# ESC.net
KiCad netlist of a schematic drawn in Altium Designer
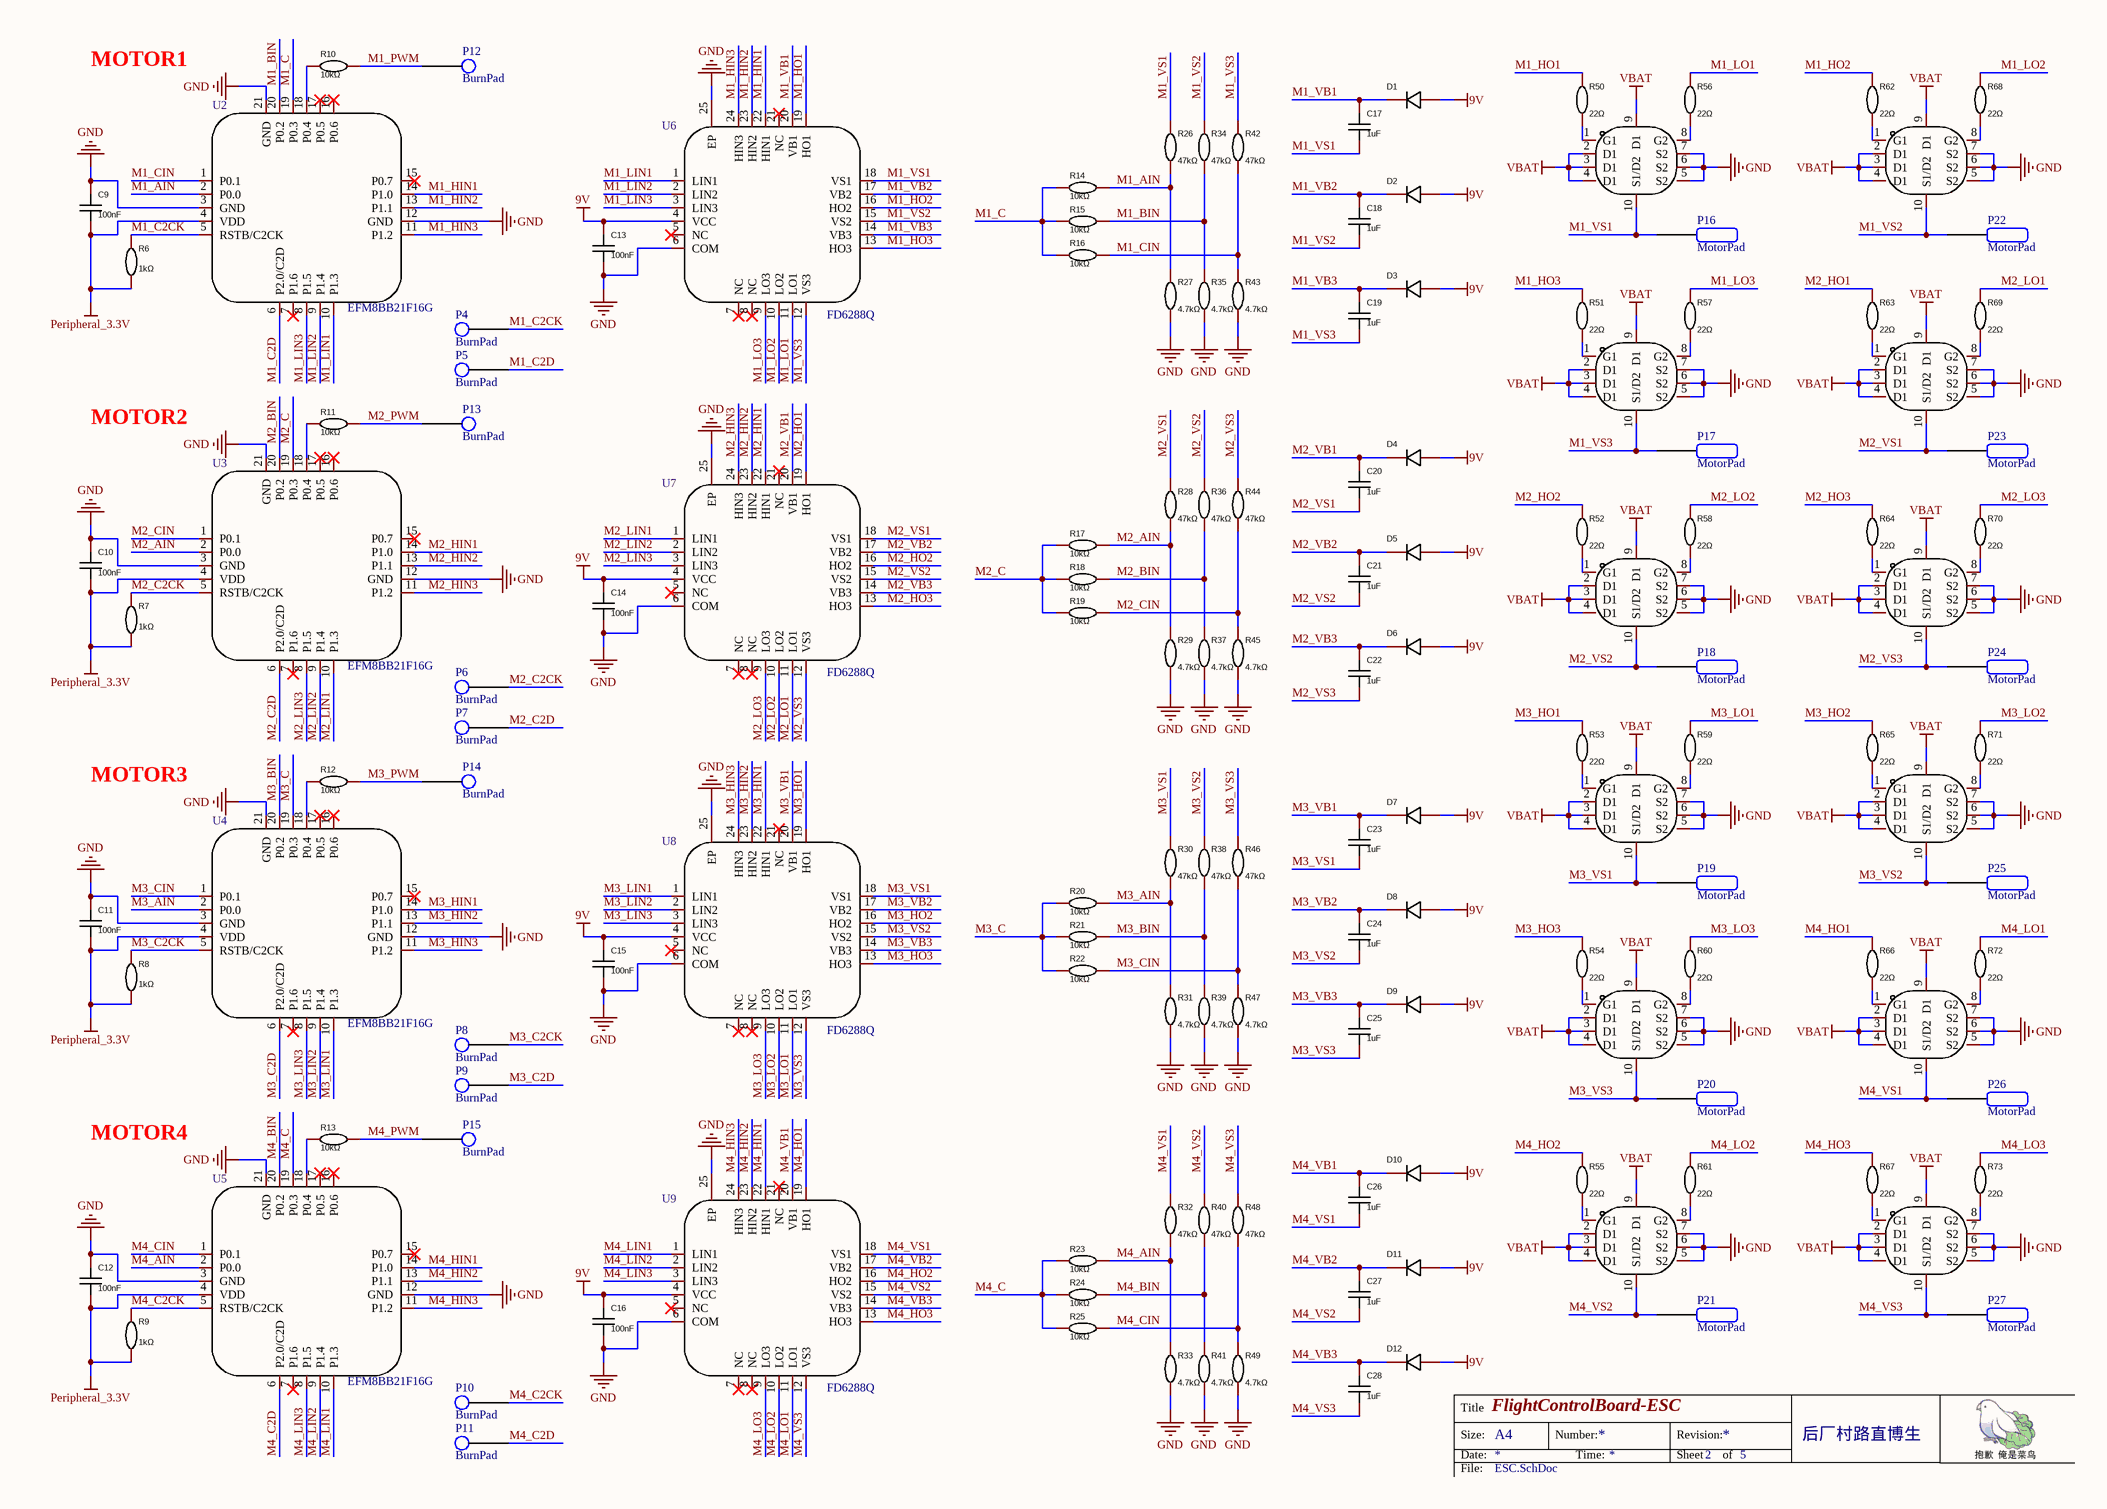
[diagram p0: ESC.SchDoc]

(export (version "E")
  (design (tool "Eeschema 10.0.6"))
  (components
    (comp (ref "C9")
      (value "100nF")
      (footprint "C0201")
      (libsource (lib "Capacitor") (part "CC0603KRX7R9BB104"))
    )
    (comp (ref "C10")
      (value "100nF")
      (footprint "C0201")
      (libsource (lib "Capacitor") (part "CC0603KRX7R9BB104"))
    )
    (comp (ref "C11")
      (value "100nF")
      (footprint "C0201")
      (libsource (lib "Capacitor") (part "CC0603KRX7R9BB104"))
    )
    (comp (ref "C12")
      (value "100nF")
      (footprint "C0201")
      (libsource (lib "Capacitor") (part "CC0603KRX7R9BB104"))
    )
    (comp (ref "C13")
      (value "100nF")
      (footprint "C0201")
      (libsource (lib "Capacitor") (part "CC0603KRX7R9BB104"))
    )
    (comp (ref "C14")
      (value "100nF")
      (footprint "C0201")
      (libsource (lib "Capacitor") (part "CC0603KRX7R9BB104"))
    )
    (comp (ref "C15")
      (value "100nF")
      (footprint "C0201")
      (libsource (lib "Capacitor") (part "CC0603KRX7R9BB104"))
    )
    (comp (ref "C16")
      (value "100nF")
      (footprint "C0201")
      (libsource (lib "Capacitor") (part "CC0603KRX7R9BB104"))
    )
    (comp (ref "C17")
      (value "1uF")
      (footprint "C0402")
      (libsource (lib "Capacitor") (part "CC0603KRX7R9BB104"))
    )
    (comp (ref "C18")
      (value "1uF")
      (footprint "C0402")
      (libsource (lib "Capacitor") (part "CC0603KRX7R9BB104"))
    )
    (comp (ref "C19")
      (value "1uF")
      (footprint "C0402")
      (libsource (lib "Capacitor") (part "CC0603KRX7R9BB104"))
    )
    (comp (ref "C20")
      (value "1uF")
      (footprint "C0402")
      (libsource (lib "Capacitor") (part "CC0603KRX7R9BB104"))
    )
    (comp (ref "C21")
      (value "1uF")
      (footprint "C0402")
      (libsource (lib "Capacitor") (part "CC0603KRX7R9BB104"))
    )
    (comp (ref "C22")
      (value "1uF")
      (footprint "C0402")
      (libsource (lib "Capacitor") (part "CC0603KRX7R9BB104"))
    )
    (comp (ref "C23")
      (value "1uF")
      (footprint "C0402")
      (libsource (lib "Capacitor") (part "CC0603KRX7R9BB104"))
    )
    (comp (ref "C24")
      (value "1uF")
      (footprint "C0402")
      (libsource (lib "Capacitor") (part "CC0603KRX7R9BB104"))
    )
    (comp (ref "C25")
      (value "1uF")
      (footprint "C0402")
      (libsource (lib "Capacitor") (part "CC0603KRX7R9BB104"))
    )
    (comp (ref "C26")
      (value "1uF")
      (footprint "C0402")
      (libsource (lib "Capacitor") (part "CC0603KRX7R9BB104"))
    )
    (comp (ref "C27")
      (value "1uF")
      (footprint "C0402")
      (libsource (lib "Capacitor") (part "CC0603KRX7R9BB104"))
    )
    (comp (ref "C28")
      (value "1uF")
      (footprint "C0402")
      (libsource (lib "Capacitor") (part "CC0603KRX7R9BB104"))
    )
    (comp (ref "D1")
      (value "1N4148WT T4")
      (footprint "SOD-523")
      (fields (field (name "MANUFACTURER") "CJ(江苏长电/长晶)"))
      (libsource (lib "Diode") (part "1N4148WT T4"))
    )
    (comp (ref "D2")
      (value "1N4148WT T4")
      (footprint "SOD-523")
      (fields (field (name "MANUFACTURER") "CJ(江苏长电/长晶)"))
      (libsource (lib "Diode") (part "1N4148WT T4"))
    )
    (comp (ref "D3")
      (value "1N4148WT T4")
      (footprint "SOD-523")
      (fields (field (name "MANUFACTURER") "CJ(江苏长电/长晶)"))
      (libsource (lib "Diode") (part "1N4148WT T4"))
    )
    (comp (ref "D4")
      (value "1N4148WT T4")
      (footprint "SOD-523")
      (fields (field (name "MANUFACTURER") "CJ(江苏长电/长晶)"))
      (libsource (lib "Diode") (part "1N4148WT T4"))
    )
    (comp (ref "D5")
      (value "1N4148WT T4")
      (footprint "SOD-523")
      (fields (field (name "MANUFACTURER") "CJ(江苏长电/长晶)"))
      (libsource (lib "Diode") (part "1N4148WT T4"))
    )
    (comp (ref "D6")
      (value "1N4148WT T4")
      (footprint "SOD-523")
      (fields (field (name "MANUFACTURER") "CJ(江苏长电/长晶)"))
      (libsource (lib "Diode") (part "1N4148WT T4"))
    )
    (comp (ref "D7")
      (value "1N4148WT T4")
      (footprint "SOD-523")
      (fields (field (name "MANUFACTURER") "CJ(江苏长电/长晶)"))
      (libsource (lib "Diode") (part "1N4148WT T4"))
    )
    (comp (ref "D8")
      (value "1N4148WT T4")
      (footprint "SOD-523")
      (fields (field (name "MANUFACTURER") "CJ(江苏长电/长晶)"))
      (libsource (lib "Diode") (part "1N4148WT T4"))
    )
    (comp (ref "D9")
      (value "1N4148WT T4")
      (footprint "SOD-523")
      (fields (field (name "MANUFACTURER") "CJ(江苏长电/长晶)"))
      (libsource (lib "Diode") (part "1N4148WT T4"))
    )
    (comp (ref "D10")
      (value "1N4148WT T4")
      (footprint "SOD-523")
      (fields (field (name "MANUFACTURER") "CJ(江苏长电/长晶)"))
      (libsource (lib "Diode") (part "1N4148WT T4"))
    )
    (comp (ref "D11")
      (value "1N4148WT T4")
      (footprint "SOD-523")
      (fields (field (name "MANUFACTURER") "CJ(江苏长电/长晶)"))
      (libsource (lib "Diode") (part "1N4148WT T4"))
    )
    (comp (ref "D12")
      (value "1N4148WT T4")
      (footprint "SOD-523")
      (fields (field (name "MANUFACTURER") "CJ(江苏长电/长晶)"))
      (libsource (lib "Diode") (part "1N4148WT T4"))
    )
    (comp (ref "P4") (value "BurnPad") (footprint "BurnPad_0.5mm") (libsource (lib "Pad") (part "BurnPad")))
    (comp (ref "P5") (value "BurnPad") (footprint "BurnPad_0.5mm") (libsource (lib "Pad") (part "BurnPad")))
    (comp (ref "P6") (value "BurnPad") (footprint "BurnPad_0.5mm") (libsource (lib "Pad") (part "BurnPad")))
    (comp (ref "P7") (value "BurnPad") (footprint "BurnPad_0.5mm") (libsource (lib "Pad") (part "BurnPad")))
    (comp (ref "P8") (value "BurnPad") (footprint "BurnPad_0.5mm") (libsource (lib "Pad") (part "BurnPad")))
    (comp (ref "P9") (value "BurnPad") (footprint "BurnPad_0.5mm") (libsource (lib "Pad") (part "BurnPad")))
    (comp (ref "P10") (value "BurnPad") (footprint "BurnPad_0.5mm") (libsource (lib "Pad") (part "BurnPad")))
    (comp (ref "P11") (value "BurnPad") (footprint "BurnPad_0.5mm") (libsource (lib "Pad") (part "BurnPad")))
    (comp (ref "P12") (value "BurnPad") (footprint "BurnPad_0.8mm") (libsource (lib "Pad") (part "BurnPad")))
    (comp (ref "P13") (value "BurnPad") (footprint "BurnPad_0.8mm") (libsource (lib "Pad") (part "BurnPad")))
    (comp (ref "P14") (value "BurnPad") (footprint "BurnPad_0.8mm") (libsource (lib "Pad") (part "BurnPad")))
    (comp (ref "P15") (value "BurnPad") (footprint "BurnPad_0.8mm") (libsource (lib "Pad") (part "BurnPad")))
    (comp (ref "P16")
      (value "MotorPad")
      (footprint "MOTOR HALF HOLE")
      (libsource (lib "Pad") (part "MotorPad"))
    )
    (comp (ref "P17")
      (value "MotorPad")
      (footprint "MOTOR HALF HOLE")
      (libsource (lib "Pad") (part "MotorPad"))
    )
    (comp (ref "P18")
      (value "MotorPad")
      (footprint "MOTOR HALF HOLE")
      (libsource (lib "Pad") (part "MotorPad"))
    )
    (comp (ref "P19")
      (value "MotorPad")
      (footprint "MOTOR HALF HOLE")
      (libsource (lib "Pad") (part "MotorPad"))
    )
    (comp (ref "P20")
      (value "MotorPad")
      (footprint "MOTOR HALF HOLE")
      (libsource (lib "Pad") (part "MotorPad"))
    )
    (comp (ref "P21")
      (value "MotorPad")
      (footprint "MOTOR HALF HOLE")
      (libsource (lib "Pad") (part "MotorPad"))
    )
    (comp (ref "P22")
      (value "MotorPad")
      (footprint "MOTOR HALF HOLE")
      (libsource (lib "Pad") (part "MotorPad"))
    )
    (comp (ref "P23")
      (value "MotorPad")
      (footprint "MOTOR HALF HOLE")
      (libsource (lib "Pad") (part "MotorPad"))
    )
    (comp (ref "P24")
      (value "MotorPad")
      (footprint "MOTOR HALF HOLE")
      (libsource (lib "Pad") (part "MotorPad"))
    )
    (comp (ref "P25")
      (value "MotorPad")
      (footprint "MOTOR HALF HOLE")
      (libsource (lib "Pad") (part "MotorPad"))
    )
    (comp (ref "P26")
      (value "MotorPad")
      (footprint "MOTOR HALF HOLE")
      (libsource (lib "Pad") (part "MotorPad"))
    )
    (comp (ref "P27")
      (value "MotorPad")
      (footprint "MOTOR HALF HOLE")
      (libsource (lib "Pad") (part "MotorPad"))
    )
    (comp (ref "Q1")
      (value "AON7934")
      (footprint "DFN-8")
      (fields (field (name "MANUFACTURER") "AOS"))
      (libsource (lib "MOS") (part "AON7934"))
    )
    (comp (ref "Q2")
      (value "AON7934")
      (footprint "DFN-8")
      (fields (field (name "MANUFACTURER") "AOS"))
      (libsource (lib "MOS") (part "AON7934"))
    )
    (comp (ref "Q3")
      (value "AON7934")
      (footprint "DFN-8")
      (fields (field (name "MANUFACTURER") "AOS"))
      (libsource (lib "MOS") (part "AON7934"))
    )
    (comp (ref "Q4")
      (value "AON7934")
      (footprint "DFN-8")
      (fields (field (name "MANUFACTURER") "AOS"))
      (libsource (lib "MOS") (part "AON7934"))
    )
    (comp (ref "Q5")
      (value "AON7934")
      (footprint "DFN-8")
      (fields (field (name "MANUFACTURER") "AOS"))
      (libsource (lib "MOS") (part "AON7934"))
    )
    (comp (ref "Q6")
      (value "AON7934")
      (footprint "DFN-8")
      (fields (field (name "MANUFACTURER") "AOS"))
      (libsource (lib "MOS") (part "AON7934"))
    )
    (comp (ref "Q7")
      (value "AON7934")
      (footprint "DFN-8")
      (fields (field (name "MANUFACTURER") "AOS"))
      (libsource (lib "MOS") (part "AON7934"))
    )
    (comp (ref "Q8")
      (value "AON7934")
      (footprint "DFN-8")
      (fields (field (name "MANUFACTURER") "AOS"))
      (libsource (lib "MOS") (part "AON7934"))
    )
    (comp (ref "Q9")
      (value "AON7934")
      (footprint "DFN-8")
      (fields (field (name "MANUFACTURER") "AOS"))
      (libsource (lib "MOS") (part "AON7934"))
    )
    (comp (ref "Q10")
      (value "AON7934")
      (footprint "DFN-8")
      (fields (field (name "MANUFACTURER") "AOS"))
      (libsource (lib "MOS") (part "AON7934"))
    )
    (comp (ref "Q11")
      (value "AON7934")
      (footprint "DFN-8")
      (fields (field (name "MANUFACTURER") "AOS"))
      (libsource (lib "MOS") (part "AON7934"))
    )
    (comp (ref "Q12")
      (value "AON7934")
      (footprint "DFN-8")
      (fields (field (name "MANUFACTURER") "AOS"))
      (libsource (lib "MOS") (part "AON7934"))
    )
    (comp (ref "R6") (value "1kΩ") (footprint "R0201") (libsource (lib "Resistor") (part "0603WAF1002T5E")))
    (comp (ref "R7") (value "1kΩ") (footprint "R0201") (libsource (lib "Resistor") (part "0603WAF1002T5E")))
    (comp (ref "R8") (value "1kΩ") (footprint "R0201") (libsource (lib "Resistor") (part "0603WAF1002T5E")))
    (comp (ref "R9") (value "1kΩ") (footprint "R0201") (libsource (lib "Resistor") (part "0603WAF1002T5E")))
    (comp (ref "R10") (value "10kΩ") (footprint "R0201") (libsource (lib "Resistor") (part "0603WAF1002T5E")))
    (comp (ref "R11") (value "10kΩ") (footprint "R0201") (libsource (lib "Resistor") (part "0603WAF1002T5E")))
    (comp (ref "R12") (value "10kΩ") (footprint "R0201") (libsource (lib "Resistor") (part "0603WAF1002T5E")))
    (comp (ref "R13") (value "10kΩ") (footprint "R0201") (libsource (lib "Resistor") (part "0603WAF1002T5E")))
    (comp (ref "R14") (value "10kΩ") (footprint "R0201") (libsource (lib "Resistor") (part "0603WAF1002T5E")))
    (comp (ref "R15") (value "10kΩ") (footprint "R0201") (libsource (lib "Resistor") (part "0603WAF1002T5E")))
    (comp (ref "R16") (value "10kΩ") (footprint "R0201") (libsource (lib "Resistor") (part "0603WAF1002T5E")))
    (comp (ref "R17") (value "10kΩ") (footprint "R0201") (libsource (lib "Resistor") (part "0603WAF1002T5E")))
    (comp (ref "R18") (value "10kΩ") (footprint "R0201") (libsource (lib "Resistor") (part "0603WAF1002T5E")))
    (comp (ref "R19") (value "10kΩ") (footprint "R0201") (libsource (lib "Resistor") (part "0603WAF1002T5E")))
    (comp (ref "R20") (value "10kΩ") (footprint "R0201") (libsource (lib "Resistor") (part "0603WAF1002T5E")))
    (comp (ref "R21") (value "10kΩ") (footprint "R0201") (libsource (lib "Resistor") (part "0603WAF1002T5E")))
    (comp (ref "R22") (value "10kΩ") (footprint "R0201") (libsource (lib "Resistor") (part "0603WAF1002T5E")))
    (comp (ref "R23") (value "10kΩ") (footprint "R0201") (libsource (lib "Resistor") (part "0603WAF1002T5E")))
    (comp (ref "R24") (value "10kΩ") (footprint "R0201") (libsource (lib "Resistor") (part "0603WAF1002T5E")))
    (comp (ref "R25") (value "10kΩ") (footprint "R0201") (libsource (lib "Resistor") (part "0603WAF1002T5E")))
    (comp (ref "R26") (value "47kΩ") (footprint "R0201") (libsource (lib "Resistor") (part "0603WAF1002T5E")))
    (comp (ref "R27")
      (value "4.7kΩ")
      (footprint "R0201")
      (libsource (lib "Resistor") (part "0603WAF1002T5E"))
    )
    (comp (ref "R28") (value "47kΩ") (footprint "R0201") (libsource (lib "Resistor") (part "0603WAF1002T5E")))
    (comp (ref "R29")
      (value "4.7kΩ")
      (footprint "R0201")
      (libsource (lib "Resistor") (part "0603WAF1002T5E"))
    )
    (comp (ref "R30") (value "47kΩ") (footprint "R0201") (libsource (lib "Resistor") (part "0603WAF1002T5E")))
    (comp (ref "R31")
      (value "4.7kΩ")
      (footprint "R0201")
      (libsource (lib "Resistor") (part "0603WAF1002T5E"))
    )
    (comp (ref "R32") (value "47kΩ") (footprint "R0201") (libsource (lib "Resistor") (part "0603WAF1002T5E")))
    (comp (ref "R33")
      (value "4.7kΩ")
      (footprint "R0201")
      (libsource (lib "Resistor") (part "0603WAF1002T5E"))
    )
    (comp (ref "R34") (value "47kΩ") (footprint "R0201") (libsource (lib "Resistor") (part "0603WAF1002T5E")))
    (comp (ref "R35")
      (value "4.7kΩ")
      (footprint "R0201")
      (libsource (lib "Resistor") (part "0603WAF1002T5E"))
    )
    (comp (ref "R36") (value "47kΩ") (footprint "R0201") (libsource (lib "Resistor") (part "0603WAF1002T5E")))
    (comp (ref "R37")
      (value "4.7kΩ")
      (footprint "R0201")
      (libsource (lib "Resistor") (part "0603WAF1002T5E"))
    )
    (comp (ref "R38") (value "47kΩ") (footprint "R0201") (libsource (lib "Resistor") (part "0603WAF1002T5E")))
    (comp (ref "R39")
      (value "4.7kΩ")
      (footprint "R0201")
      (libsource (lib "Resistor") (part "0603WAF1002T5E"))
    )
    (comp (ref "R40") (value "47kΩ") (footprint "R0201") (libsource (lib "Resistor") (part "0603WAF1002T5E")))
    (comp (ref "R41")
      (value "4.7kΩ")
      (footprint "R0201")
      (libsource (lib "Resistor") (part "0603WAF1002T5E"))
    )
    (comp (ref "R42") (value "47kΩ") (footprint "R0201") (libsource (lib "Resistor") (part "0603WAF1002T5E")))
    (comp (ref "R43")
      (value "4.7kΩ")
      (footprint "R0201")
      (libsource (lib "Resistor") (part "0603WAF1002T5E"))
    )
    (comp (ref "R44") (value "47kΩ") (footprint "R0201") (libsource (lib "Resistor") (part "0603WAF1002T5E")))
    (comp (ref "R45")
      (value "4.7kΩ")
      (footprint "R0201")
      (libsource (lib "Resistor") (part "0603WAF1002T5E"))
    )
    (comp (ref "R46") (value "47kΩ") (footprint "R0201") (libsource (lib "Resistor") (part "0603WAF1002T5E")))
    (comp (ref "R47")
      (value "4.7kΩ")
      (footprint "R0201")
      (libsource (lib "Resistor") (part "0603WAF1002T5E"))
    )
    (comp (ref "R48") (value "47kΩ") (footprint "R0201") (libsource (lib "Resistor") (part "0603WAF1002T5E")))
    (comp (ref "R49")
      (value "4.7kΩ")
      (footprint "R0201")
      (libsource (lib "Resistor") (part "0603WAF1002T5E"))
    )
    (comp (ref "R50") (value "22Ω") (footprint "R0201") (libsource (lib "Resistor") (part "0603WAF1002T5E")))
    (comp (ref "R51") (value "22Ω") (footprint "R0201") (libsource (lib "Resistor") (part "0603WAF1002T5E")))
    (comp (ref "R52") (value "22Ω") (footprint "R0201") (libsource (lib "Resistor") (part "0603WAF1002T5E")))
    (comp (ref "R53") (value "22Ω") (footprint "R0201") (libsource (lib "Resistor") (part "0603WAF1002T5E")))
    (comp (ref "R54") (value "22Ω") (footprint "R0201") (libsource (lib "Resistor") (part "0603WAF1002T5E")))
    (comp (ref "R55") (value "22Ω") (footprint "R0201") (libsource (lib "Resistor") (part "0603WAF1002T5E")))
    (comp (ref "R56") (value "22Ω") (footprint "R0201") (libsource (lib "Resistor") (part "0603WAF1002T5E")))
    (comp (ref "R57") (value "22Ω") (footprint "R0201") (libsource (lib "Resistor") (part "0603WAF1002T5E")))
    (comp (ref "R58") (value "22Ω") (footprint "R0201") (libsource (lib "Resistor") (part "0603WAF1002T5E")))
    (comp (ref "R59") (value "22Ω") (footprint "R0201") (libsource (lib "Resistor") (part "0603WAF1002T5E")))
    (comp (ref "R60") (value "22Ω") (footprint "R0201") (libsource (lib "Resistor") (part "0603WAF1002T5E")))
    (comp (ref "R61") (value "22Ω") (footprint "R0201") (libsource (lib "Resistor") (part "0603WAF1002T5E")))
    (comp (ref "R62") (value "22Ω") (footprint "R0201") (libsource (lib "Resistor") (part "0603WAF1002T5E")))
    (comp (ref "R63") (value "22Ω") (footprint "R0201") (libsource (lib "Resistor") (part "0603WAF1002T5E")))
    (comp (ref "R64") (value "22Ω") (footprint "R0201") (libsource (lib "Resistor") (part "0603WAF1002T5E")))
    (comp (ref "R65") (value "22Ω") (footprint "R0201") (libsource (lib "Resistor") (part "0603WAF1002T5E")))
    (comp (ref "R66") (value "22Ω") (footprint "R0201") (libsource (lib "Resistor") (part "0603WAF1002T5E")))
    (comp (ref "R67") (value "22Ω") (footprint "R0201") (libsource (lib "Resistor") (part "0603WAF1002T5E")))
    (comp (ref "R68") (value "22Ω") (footprint "R0201") (libsource (lib "Resistor") (part "0603WAF1002T5E")))
    (comp (ref "R69") (value "22Ω") (footprint "R0201") (libsource (lib "Resistor") (part "0603WAF1002T5E")))
    (comp (ref "R70") (value "22Ω") (footprint "R0201") (libsource (lib "Resistor") (part "0603WAF1002T5E")))
    (comp (ref "R71") (value "22Ω") (footprint "R0201") (libsource (lib "Resistor") (part "0603WAF1002T5E")))
    (comp (ref "R72") (value "22Ω") (footprint "R0201") (libsource (lib "Resistor") (part "0603WAF1002T5E")))
    (comp (ref "R73") (value "22Ω") (footprint "R0201") (libsource (lib "Resistor") (part "0603WAF1002T5E")))
    (comp (ref "U2")
      (value "EFM8BB21F16G")
      (footprint "QFN-20_L3.0-W3.0-P0.50-BL-EP1.7_EFM8BB21F16G")
      (fields
        (field (name "MANUFACTURER") "SILICON LABS(芯科)")
        (field (name "MANUFACTURER PART") "EFM8BB21F16G-C-QFN20R")
      )
      (libsource (lib "ESC_Drive") (part "EFM8BB21F16G"))
    )
    (comp (ref "U3")
      (value "EFM8BB21F16G")
      (footprint "QFN-20_L3.0-W3.0-P0.50-BL-EP1.7_EFM8BB21F16G")
      (fields
        (field (name "MANUFACTURER") "SILICON LABS(芯科)")
        (field (name "MANUFACTURER PART") "EFM8BB21F16G-C-QFN20R")
      )
      (libsource (lib "ESC_Drive") (part "EFM8BB21F16G"))
    )
    (comp (ref "U4")
      (value "EFM8BB21F16G")
      (footprint "QFN-20_L3.0-W3.0-P0.50-BL-EP1.7_EFM8BB21F16G")
      (fields
        (field (name "MANUFACTURER") "SILICON LABS(芯科)")
        (field (name "MANUFACTURER PART") "EFM8BB21F16G-C-QFN20R")
      )
      (libsource (lib "ESC_Drive") (part "EFM8BB21F16G"))
    )
    (comp (ref "U5")
      (value "EFM8BB21F16G")
      (footprint "QFN-20_L3.0-W3.0-P0.50-BL-EP1.7_EFM8BB21F16G")
      (fields
        (field (name "MANUFACTURER") "SILICON LABS(芯科)")
        (field (name "MANUFACTURER PART") "EFM8BB21F16G-C-QFN20R")
      )
      (libsource (lib "ESC_Drive") (part "EFM8BB21F16G"))
    )
    (comp (ref "U6")
      (value "FD6288Q")
      (footprint "QFN-24_L4.0-W4.0-P0.50-BL-EP2.6")
      (fields (field (name "MANUFACTURER") "Fortior Tech(峰岹)"))
      (libsource (lib "ESC_Drive") (part "FD6288Q"))
    )
    (comp (ref "U7")
      (value "FD6288Q")
      (footprint "QFN-24_L4.0-W4.0-P0.50-BL-EP2.6")
      (fields (field (name "MANUFACTURER") "Fortior Tech(峰岹)"))
      (libsource (lib "ESC_Drive") (part "FD6288Q"))
    )
    (comp (ref "U8")
      (value "FD6288Q")
      (footprint "QFN-24_L4.0-W4.0-P0.50-BL-EP2.6")
      (fields (field (name "MANUFACTURER") "Fortior Tech(峰岹)"))
      (libsource (lib "ESC_Drive") (part "FD6288Q"))
    )
    (comp (ref "U9")
      (value "FD6288Q")
      (footprint "QFN-24_L4.0-W4.0-P0.50-BL-EP2.6")
      (fields (field (name "MANUFACTURER") "Fortior Tech(峰岹)"))
      (libsource (lib "ESC_Drive") (part "FD6288Q"))
    )
  )
  (nets
    (net (code "1") (name "/M1_AIN") (class "Default")
      (node (ref "R14") (pin "2") (pinfunction "2_2") (pintype "passive"))
      (node (ref "R26") (pin "1") (pinfunction "1_1") (pintype "passive"))
      (node (ref "R27") (pin "2") (pinfunction "2_2") (pintype "passive"))
      (node (ref "U2") (pin "2") (pinfunction "P0.0_2") (pintype "passive"))
    )
    (net (code "2") (name "/M1_BIN") (class "Default")
      (node (ref "R15") (pin "2") (pinfunction "2_2") (pintype "passive"))
      (node (ref "R34") (pin "1") (pinfunction "1_1") (pintype "passive"))
      (node (ref "R35") (pin "2") (pinfunction "2_2") (pintype "passive"))
      (node (ref "U2") (pin "20") (pinfunction "P0.2_20") (pintype "passive"))
    )
    (net (code "3") (name "/M1_C") (class "Default")
      (node (ref "R14") (pin "1") (pinfunction "1_1") (pintype "passive"))
      (node (ref "R15") (pin "1") (pinfunction "1_1") (pintype "passive"))
      (node (ref "R16") (pin "1") (pinfunction "1_1") (pintype "passive"))
      (node (ref "U2") (pin "19") (pinfunction "P0.3_19") (pintype "passive"))
    )
    (net (code "4") (name "/M1_C2CK") (class "Default")
      (node (ref "P4") (pin "1") (pinfunction "1_1") (pintype "passive"))
      (node (ref "R6") (pin "2") (pinfunction "2_2") (pintype "passive"))
      (node (ref "U2") (pin "5") (pinfunction "RSTB/C2CK_5") (pintype "passive"))
    )
    (net (code "5") (name "/M1_C2D") (class "Default")
      (node (ref "P5") (pin "1") (pinfunction "1_1") (pintype "passive"))
      (node (ref "U2") (pin "6") (pinfunction "P2.0/C2D_6") (pintype "passive"))
    )
    (net (code "6") (name "/M1_CIN") (class "Default")
      (node (ref "R16") (pin "2") (pinfunction "2_2") (pintype "passive"))
      (node (ref "R42") (pin "1") (pinfunction "1_1") (pintype "passive"))
      (node (ref "R43") (pin "2") (pinfunction "2_2") (pintype "passive"))
      (node (ref "U2") (pin "1") (pinfunction "P0.1_1") (pintype "passive"))
    )
    (net (code "7") (name "/M1_HIN1") (class "Default")
      (node (ref "U2") (pin "14") (pinfunction "P1.0_14") (pintype "passive"))
      (node (ref "U6") (pin "22") (pinfunction "HIN1_22") (pintype "passive"))
    )
    (net (code "8") (name "/M1_HIN2") (class "Default")
      (node (ref "U2") (pin "13") (pinfunction "P1.1_13") (pintype "passive"))
      (node (ref "U6") (pin "23") (pinfunction "HIN2_23") (pintype "passive"))
    )
    (net (code "9") (name "/M1_HIN3") (class "Default")
      (node (ref "U2") (pin "11") (pinfunction "P1.2_11") (pintype "passive"))
      (node (ref "U6") (pin "24") (pinfunction "HIN3_24") (pintype "passive"))
    )
    (net (code "10") (name "/M1_HO1") (class "Default")
      (node (ref "R50") (pin "2") (pinfunction "2_2") (pintype "passive"))
      (node (ref "U6") (pin "19") (pinfunction "HO1_19") (pintype "passive"))
    )
    (net (code "11") (name "/M1_HO2") (class "Default")
      (node (ref "R62") (pin "2") (pinfunction "2_2") (pintype "passive"))
      (node (ref "U6") (pin "16") (pinfunction "HO2_16") (pintype "passive"))
    )
    (net (code "12") (name "/M1_HO3") (class "Default")
      (node (ref "R51") (pin "2") (pinfunction "2_2") (pintype "passive"))
      (node (ref "U6") (pin "13") (pinfunction "HO3_13") (pintype "passive"))
    )
    (net (code "13") (name "/M1_LIN1") (class "Default")
      (node (ref "U2") (pin "10") (pinfunction "P1.3_10") (pintype "passive"))
      (node (ref "U6") (pin "1") (pinfunction "LIN1_1") (pintype "passive"))
    )
    (net (code "14") (name "/M1_LIN2") (class "Default")
      (node (ref "U2") (pin "9") (pinfunction "P1.4_9") (pintype "passive"))
      (node (ref "U6") (pin "2") (pinfunction "LIN2_2") (pintype "passive"))
    )
    (net (code "15") (name "/M1_LIN3") (class "Default")
      (node (ref "U2") (pin "8") (pinfunction "P1.5_8") (pintype "passive"))
      (node (ref "U6") (pin "3") (pinfunction "LIN3_3") (pintype "passive"))
    )
    (net (code "16") (name "/M1_LO1") (class "Default")
      (node (ref "R56") (pin "2") (pinfunction "2_2") (pintype "passive"))
      (node (ref "U6") (pin "11") (pinfunction "LO1_11") (pintype "passive"))
    )
    (net (code "17") (name "/M1_LO2") (class "Default")
      (node (ref "R68") (pin "2") (pinfunction "2_2") (pintype "passive"))
      (node (ref "U6") (pin "10") (pinfunction "LO2_10") (pintype "passive"))
    )
    (net (code "18") (name "/M1_LO3") (class "Default")
      (node (ref "R57") (pin "2") (pinfunction "2_2") (pintype "passive"))
      (node (ref "U6") (pin "9") (pinfunction "LO3_9") (pintype "passive"))
    )
    (net (code "19") (name "/M1_PWM") (class "Default")
      (node (ref "P12") (pin "1") (pinfunction "1_1") (pintype "passive"))
      (node (ref "R10") (pin "2") (pinfunction "2_2") (pintype "passive"))
    )
    (net (code "20") (name "/M1_VB1") (class "Default")
      (node (ref "C17") (pin "2") (pinfunction "2_2") (pintype "passive"))
      (node (ref "D1") (pin "1") (pinfunction "K_1") (pintype "passive"))
      (node (ref "U6") (pin "20") (pinfunction "VB1_20") (pintype "passive"))
    )
    (net (code "21") (name "/M1_VB2") (class "Default")
      (node (ref "C18") (pin "2") (pinfunction "2_2") (pintype "passive"))
      (node (ref "D2") (pin "1") (pinfunction "K_1") (pintype "passive"))
      (node (ref "U6") (pin "17") (pinfunction "VB2_17") (pintype "passive"))
    )
    (net (code "22") (name "/M1_VB3") (class "Default")
      (node (ref "C19") (pin "2") (pinfunction "2_2") (pintype "passive"))
      (node (ref "D3") (pin "1") (pinfunction "K_1") (pintype "passive"))
      (node (ref "U6") (pin "14") (pinfunction "VB3_14") (pintype "passive"))
    )
    (net (code "23") (name "/M1_VS1") (class "Default")
      (node (ref "C17") (pin "1") (pinfunction "1_1") (pintype "passive"))
      (node (ref "P16") (pin "1") (pinfunction "1_1") (pintype "passive"))
      (node (ref "Q1") (pin "10") (pinfunction "S1/D2_10") (pintype "passive"))
      (node (ref "R26") (pin "2") (pinfunction "2_2") (pintype "passive"))
      (node (ref "U6") (pin "18") (pinfunction "VS1_18") (pintype "passive"))
    )
    (net (code "24") (name "/M1_VS2") (class "Default")
      (node (ref "C18") (pin "1") (pinfunction "1_1") (pintype "passive"))
      (node (ref "P22") (pin "1") (pinfunction "1_1") (pintype "passive"))
      (node (ref "Q7") (pin "10") (pinfunction "S1/D2_10") (pintype "passive"))
      (node (ref "R34") (pin "2") (pinfunction "2_2") (pintype "passive"))
      (node (ref "U6") (pin "15") (pinfunction "VS2_15") (pintype "passive"))
    )
    (net (code "25") (name "/M1_VS3") (class "Default")
      (node (ref "C19") (pin "1") (pinfunction "1_1") (pintype "passive"))
      (node (ref "P17") (pin "1") (pinfunction "1_1") (pintype "passive"))
      (node (ref "Q2") (pin "10") (pinfunction "S1/D2_10") (pintype "passive"))
      (node (ref "R42") (pin "2") (pinfunction "2_2") (pintype "passive"))
      (node (ref "U6") (pin "12") (pinfunction "VS3_12") (pintype "passive"))
    )
    (net (code "26") (name "/M2_AIN") (class "Default")
      (node (ref "R17") (pin "2") (pinfunction "2_2") (pintype "passive"))
      (node (ref "R28") (pin "1") (pinfunction "1_1") (pintype "passive"))
      (node (ref "R29") (pin "2") (pinfunction "2_2") (pintype "passive"))
      (node (ref "U3") (pin "2") (pinfunction "P0.0_2") (pintype "passive"))
    )
    (net (code "27") (name "/M2_BIN") (class "Default")
      (node (ref "R18") (pin "2") (pinfunction "2_2") (pintype "passive"))
      (node (ref "R36") (pin "1") (pinfunction "1_1") (pintype "passive"))
      (node (ref "R37") (pin "2") (pinfunction "2_2") (pintype "passive"))
      (node (ref "U3") (pin "20") (pinfunction "P0.2_20") (pintype "passive"))
    )
    (net (code "28") (name "/M2_C") (class "Default")
      (node (ref "R17") (pin "1") (pinfunction "1_1") (pintype "passive"))
      (node (ref "R18") (pin "1") (pinfunction "1_1") (pintype "passive"))
      (node (ref "R19") (pin "1") (pinfunction "1_1") (pintype "passive"))
      (node (ref "U3") (pin "19") (pinfunction "P0.3_19") (pintype "passive"))
    )
    (net (code "29") (name "/M2_C2CK") (class "Default")
      (node (ref "P6") (pin "1") (pinfunction "1_1") (pintype "passive"))
      (node (ref "R7") (pin "2") (pinfunction "2_2") (pintype "passive"))
      (node (ref "U3") (pin "5") (pinfunction "RSTB/C2CK_5") (pintype "passive"))
    )
    (net (code "30") (name "/M2_C2D") (class "Default")
      (node (ref "P7") (pin "1") (pinfunction "1_1") (pintype "passive"))
      (node (ref "U3") (pin "6") (pinfunction "P2.0/C2D_6") (pintype "passive"))
    )
    (net (code "31") (name "/M2_CIN") (class "Default")
      (node (ref "R19") (pin "2") (pinfunction "2_2") (pintype "passive"))
      (node (ref "R44") (pin "1") (pinfunction "1_1") (pintype "passive"))
      (node (ref "R45") (pin "2") (pinfunction "2_2") (pintype "passive"))
      (node (ref "U3") (pin "1") (pinfunction "P0.1_1") (pintype "passive"))
    )
    (net (code "32") (name "/M2_HIN1") (class "Default")
      (node (ref "U3") (pin "14") (pinfunction "P1.0_14") (pintype "passive"))
      (node (ref "U7") (pin "22") (pinfunction "HIN1_22") (pintype "passive"))
    )
    (net (code "33") (name "/M2_HIN2") (class "Default")
      (node (ref "U3") (pin "13") (pinfunction "P1.1_13") (pintype "passive"))
      (node (ref "U7") (pin "23") (pinfunction "HIN2_23") (pintype "passive"))
    )
    (net (code "34") (name "/M2_HIN3") (class "Default")
      (node (ref "U3") (pin "11") (pinfunction "P1.2_11") (pintype "passive"))
      (node (ref "U7") (pin "24") (pinfunction "HIN3_24") (pintype "passive"))
    )
    (net (code "35") (name "/M2_HO1") (class "Default")
      (node (ref "R63") (pin "2") (pinfunction "2_2") (pintype "passive"))
      (node (ref "U7") (pin "19") (pinfunction "HO1_19") (pintype "passive"))
    )
    (net (code "36") (name "/M2_HO2") (class "Default")
      (node (ref "R52") (pin "2") (pinfunction "2_2") (pintype "passive"))
      (node (ref "U7") (pin "16") (pinfunction "HO2_16") (pintype "passive"))
    )
    (net (code "37") (name "/M2_HO3") (class "Default")
      (node (ref "R64") (pin "2") (pinfunction "2_2") (pintype "passive"))
      (node (ref "U7") (pin "13") (pinfunction "HO3_13") (pintype "passive"))
    )
    (net (code "38") (name "/M2_LIN1") (class "Default")
      (node (ref "U3") (pin "10") (pinfunction "P1.3_10") (pintype "passive"))
      (node (ref "U7") (pin "1") (pinfunction "LIN1_1") (pintype "passive"))
    )
    (net (code "39") (name "/M2_LIN2") (class "Default")
      (node (ref "U3") (pin "9") (pinfunction "P1.4_9") (pintype "passive"))
      (node (ref "U7") (pin "2") (pinfunction "LIN2_2") (pintype "passive"))
    )
    (net (code "40") (name "/M2_LIN3") (class "Default")
      (node (ref "U3") (pin "8") (pinfunction "P1.5_8") (pintype "passive"))
      (node (ref "U7") (pin "3") (pinfunction "LIN3_3") (pintype "passive"))
    )
    (net (code "41") (name "/M2_LO1") (class "Default")
      (node (ref "R69") (pin "2") (pinfunction "2_2") (pintype "passive"))
      (node (ref "U7") (pin "11") (pinfunction "LO1_11") (pintype "passive"))
    )
    (net (code "42") (name "/M2_LO2") (class "Default")
      (node (ref "R58") (pin "2") (pinfunction "2_2") (pintype "passive"))
      (node (ref "U7") (pin "10") (pinfunction "LO2_10") (pintype "passive"))
    )
    (net (code "43") (name "/M2_LO3") (class "Default")
      (node (ref "R70") (pin "2") (pinfunction "2_2") (pintype "passive"))
      (node (ref "U7") (pin "9") (pinfunction "LO3_9") (pintype "passive"))
    )
    (net (code "44") (name "/M2_PWM") (class "Default")
      (node (ref "P13") (pin "1") (pinfunction "1_1") (pintype "passive"))
      (node (ref "R11") (pin "2") (pinfunction "2_2") (pintype "passive"))
    )
    (net (code "45") (name "/M2_VB1") (class "Default")
      (node (ref "C20") (pin "2") (pinfunction "2_2") (pintype "passive"))
      (node (ref "D4") (pin "1") (pinfunction "K_1") (pintype "passive"))
      (node (ref "U7") (pin "20") (pinfunction "VB1_20") (pintype "passive"))
    )
    (net (code "46") (name "/M2_VB2") (class "Default")
      (node (ref "C21") (pin "2") (pinfunction "2_2") (pintype "passive"))
      (node (ref "D5") (pin "1") (pinfunction "K_1") (pintype "passive"))
      (node (ref "U7") (pin "17") (pinfunction "VB2_17") (pintype "passive"))
    )
    (net (code "47") (name "/M2_VB3") (class "Default")
      (node (ref "C22") (pin "2") (pinfunction "2_2") (pintype "passive"))
      (node (ref "D6") (pin "1") (pinfunction "K_1") (pintype "passive"))
      (node (ref "U7") (pin "14") (pinfunction "VB3_14") (pintype "passive"))
    )
    (net (code "48") (name "/M2_VS1") (class "Default")
      (node (ref "C20") (pin "1") (pinfunction "1_1") (pintype "passive"))
      (node (ref "P23") (pin "1") (pinfunction "1_1") (pintype "passive"))
      (node (ref "Q8") (pin "10") (pinfunction "S1/D2_10") (pintype "passive"))
      (node (ref "R28") (pin "2") (pinfunction "2_2") (pintype "passive"))
      (node (ref "U7") (pin "18") (pinfunction "VS1_18") (pintype "passive"))
    )
    (net (code "49") (name "/M2_VS2") (class "Default")
      (node (ref "C21") (pin "1") (pinfunction "1_1") (pintype "passive"))
      (node (ref "P18") (pin "1") (pinfunction "1_1") (pintype "passive"))
      (node (ref "Q3") (pin "10") (pinfunction "S1/D2_10") (pintype "passive"))
      (node (ref "R36") (pin "2") (pinfunction "2_2") (pintype "passive"))
      (node (ref "U7") (pin "15") (pinfunction "VS2_15") (pintype "passive"))
    )
    (net (code "50") (name "/M2_VS3") (class "Default")
      (node (ref "C22") (pin "1") (pinfunction "1_1") (pintype "passive"))
      (node (ref "P24") (pin "1") (pinfunction "1_1") (pintype "passive"))
      (node (ref "Q9") (pin "10") (pinfunction "S1/D2_10") (pintype "passive"))
      (node (ref "R44") (pin "2") (pinfunction "2_2") (pintype "passive"))
      (node (ref "U7") (pin "12") (pinfunction "VS3_12") (pintype "passive"))
    )
    (net (code "51") (name "/M3_AIN") (class "Default")
      (node (ref "R20") (pin "2") (pinfunction "2_2") (pintype "passive"))
      (node (ref "R30") (pin "1") (pinfunction "1_1") (pintype "passive"))
      (node (ref "R31") (pin "2") (pinfunction "2_2") (pintype "passive"))
      (node (ref "U4") (pin "2") (pinfunction "P0.0_2") (pintype "passive"))
    )
    (net (code "52") (name "/M3_BIN") (class "Default")
      (node (ref "R21") (pin "2") (pinfunction "2_2") (pintype "passive"))
      (node (ref "R38") (pin "1") (pinfunction "1_1") (pintype "passive"))
      (node (ref "R39") (pin "2") (pinfunction "2_2") (pintype "passive"))
      (node (ref "U4") (pin "20") (pinfunction "P0.2_20") (pintype "passive"))
    )
    (net (code "53") (name "/M3_C") (class "Default")
      (node (ref "R20") (pin "1") (pinfunction "1_1") (pintype "passive"))
      (node (ref "R21") (pin "1") (pinfunction "1_1") (pintype "passive"))
      (node (ref "R22") (pin "1") (pinfunction "1_1") (pintype "passive"))
      (node (ref "U4") (pin "19") (pinfunction "P0.3_19") (pintype "passive"))
    )
    (net (code "54") (name "/M3_C2CK") (class "Default")
      (node (ref "P8") (pin "1") (pinfunction "1_1") (pintype "passive"))
      (node (ref "R8") (pin "2") (pinfunction "2_2") (pintype "passive"))
      (node (ref "U4") (pin "5") (pinfunction "RSTB/C2CK_5") (pintype "passive"))
    )
    (net (code "55") (name "/M3_C2D") (class "Default")
      (node (ref "P9") (pin "1") (pinfunction "1_1") (pintype "passive"))
      (node (ref "U4") (pin "6") (pinfunction "P2.0/C2D_6") (pintype "passive"))
    )
    (net (code "56") (name "/M3_CIN") (class "Default")
      (node (ref "R22") (pin "2") (pinfunction "2_2") (pintype "passive"))
      (node (ref "R46") (pin "1") (pinfunction "1_1") (pintype "passive"))
      (node (ref "R47") (pin "2") (pinfunction "2_2") (pintype "passive"))
      (node (ref "U4") (pin "1") (pinfunction "P0.1_1") (pintype "passive"))
    )
    (net (code "57") (name "/M3_HIN1") (class "Default")
      (node (ref "U4") (pin "14") (pinfunction "P1.0_14") (pintype "passive"))
      (node (ref "U8") (pin "22") (pinfunction "HIN1_22") (pintype "passive"))
    )
    (net (code "58") (name "/M3_HIN2") (class "Default")
      (node (ref "U4") (pin "13") (pinfunction "P1.1_13") (pintype "passive"))
      (node (ref "U8") (pin "23") (pinfunction "HIN2_23") (pintype "passive"))
    )
    (net (code "59") (name "/M3_HIN3") (class "Default")
      (node (ref "U4") (pin "11") (pinfunction "P1.2_11") (pintype "passive"))
      (node (ref "U8") (pin "24") (pinfunction "HIN3_24") (pintype "passive"))
    )
    (net (code "60") (name "/M3_HO1") (class "Default")
      (node (ref "R53") (pin "2") (pinfunction "2_2") (pintype "passive"))
      (node (ref "U8") (pin "19") (pinfunction "HO1_19") (pintype "passive"))
    )
    (net (code "61") (name "/M3_HO2") (class "Default")
      (node (ref "R65") (pin "2") (pinfunction "2_2") (pintype "passive"))
      (node (ref "U8") (pin "16") (pinfunction "HO2_16") (pintype "passive"))
    )
    (net (code "62") (name "/M3_HO3") (class "Default")
      (node (ref "R54") (pin "2") (pinfunction "2_2") (pintype "passive"))
      (node (ref "U8") (pin "13") (pinfunction "HO3_13") (pintype "passive"))
    )
    (net (code "63") (name "/M3_LIN1") (class "Default")
      (node (ref "U4") (pin "10") (pinfunction "P1.3_10") (pintype "passive"))
      (node (ref "U8") (pin "1") (pinfunction "LIN1_1") (pintype "passive"))
    )
    (net (code "64") (name "/M3_LIN2") (class "Default")
      (node (ref "U4") (pin "9") (pinfunction "P1.4_9") (pintype "passive"))
      (node (ref "U8") (pin "2") (pinfunction "LIN2_2") (pintype "passive"))
    )
    (net (code "65") (name "/M3_LIN3") (class "Default")
      (node (ref "U4") (pin "8") (pinfunction "P1.5_8") (pintype "passive"))
      (node (ref "U8") (pin "3") (pinfunction "LIN3_3") (pintype "passive"))
    )
    (net (code "66") (name "/M3_LO1") (class "Default")
      (node (ref "R59") (pin "2") (pinfunction "2_2") (pintype "passive"))
      (node (ref "U8") (pin "11") (pinfunction "LO1_11") (pintype "passive"))
    )
    (net (code "67") (name "/M3_LO2") (class "Default")
      (node (ref "R71") (pin "2") (pinfunction "2_2") (pintype "passive"))
      (node (ref "U8") (pin "10") (pinfunction "LO2_10") (pintype "passive"))
    )
    (net (code "68") (name "/M3_LO3") (class "Default")
      (node (ref "R60") (pin "2") (pinfunction "2_2") (pintype "passive"))
      (node (ref "U8") (pin "9") (pinfunction "LO3_9") (pintype "passive"))
    )
    (net (code "69") (name "/M3_PWM") (class "Default")
      (node (ref "P14") (pin "1") (pinfunction "1_1") (pintype "passive"))
      (node (ref "R12") (pin "2") (pinfunction "2_2") (pintype "passive"))
    )
    (net (code "70") (name "/M3_VB1") (class "Default")
      (node (ref "C23") (pin "2") (pinfunction "2_2") (pintype "passive"))
      (node (ref "D7") (pin "1") (pinfunction "K_1") (pintype "passive"))
      (node (ref "U8") (pin "20") (pinfunction "VB1_20") (pintype "passive"))
    )
    (net (code "71") (name "/M3_VB2") (class "Default")
      (node (ref "C24") (pin "2") (pinfunction "2_2") (pintype "passive"))
      (node (ref "D8") (pin "1") (pinfunction "K_1") (pintype "passive"))
      (node (ref "U8") (pin "17") (pinfunction "VB2_17") (pintype "passive"))
    )
    (net (code "72") (name "/M3_VB3") (class "Default")
      (node (ref "C25") (pin "2") (pinfunction "2_2") (pintype "passive"))
      (node (ref "D9") (pin "1") (pinfunction "K_1") (pintype "passive"))
      (node (ref "U8") (pin "14") (pinfunction "VB3_14") (pintype "passive"))
    )
    (net (code "73") (name "/M3_VS1") (class "Default")
      (node (ref "C23") (pin "1") (pinfunction "1_1") (pintype "passive"))
      (node (ref "P19") (pin "1") (pinfunction "1_1") (pintype "passive"))
      (node (ref "Q4") (pin "10") (pinfunction "S1/D2_10") (pintype "passive"))
      (node (ref "R30") (pin "2") (pinfunction "2_2") (pintype "passive"))
      (node (ref "U8") (pin "18") (pinfunction "VS1_18") (pintype "passive"))
    )
    (net (code "74") (name "/M3_VS2") (class "Default")
      (node (ref "C24") (pin "1") (pinfunction "1_1") (pintype "passive"))
      (node (ref "P25") (pin "1") (pinfunction "1_1") (pintype "passive"))
      (node (ref "Q10") (pin "10") (pinfunction "S1/D2_10") (pintype "passive"))
      (node (ref "R38") (pin "2") (pinfunction "2_2") (pintype "passive"))
      (node (ref "U8") (pin "15") (pinfunction "VS2_15") (pintype "passive"))
    )
    (net (code "75") (name "/M3_VS3") (class "Default")
      (node (ref "C25") (pin "1") (pinfunction "1_1") (pintype "passive"))
      (node (ref "P20") (pin "1") (pinfunction "1_1") (pintype "passive"))
      (node (ref "Q5") (pin "10") (pinfunction "S1/D2_10") (pintype "passive"))
      (node (ref "R46") (pin "2") (pinfunction "2_2") (pintype "passive"))
      (node (ref "U8") (pin "12") (pinfunction "VS3_12") (pintype "passive"))
    )
    (net (code "76") (name "/M4_AIN") (class "Default")
      (node (ref "R23") (pin "2") (pinfunction "2_2") (pintype "passive"))
      (node (ref "R32") (pin "1") (pinfunction "1_1") (pintype "passive"))
      (node (ref "R33") (pin "2") (pinfunction "2_2") (pintype "passive"))
      (node (ref "U5") (pin "2") (pinfunction "P0.0_2") (pintype "passive"))
    )
    (net (code "77") (name "/M4_BIN") (class "Default")
      (node (ref "R24") (pin "2") (pinfunction "2_2") (pintype "passive"))
      (node (ref "R40") (pin "1") (pinfunction "1_1") (pintype "passive"))
      (node (ref "R41") (pin "2") (pinfunction "2_2") (pintype "passive"))
      (node (ref "U5") (pin "20") (pinfunction "P0.2_20") (pintype "passive"))
    )
    (net (code "78") (name "/M4_C") (class "Default")
      (node (ref "R23") (pin "1") (pinfunction "1_1") (pintype "passive"))
      (node (ref "R24") (pin "1") (pinfunction "1_1") (pintype "passive"))
      (node (ref "R25") (pin "1") (pinfunction "1_1") (pintype "passive"))
      (node (ref "U5") (pin "19") (pinfunction "P0.3_19") (pintype "passive"))
    )
    (net (code "79") (name "/M4_C2CK") (class "Default")
      (node (ref "P10") (pin "1") (pinfunction "1_1") (pintype "passive"))
      (node (ref "R9") (pin "2") (pinfunction "2_2") (pintype "passive"))
      (node (ref "U5") (pin "5") (pinfunction "RSTB/C2CK_5") (pintype "passive"))
    )
    (net (code "80") (name "/M4_C2D") (class "Default")
      (node (ref "P11") (pin "1") (pinfunction "1_1") (pintype "passive"))
      (node (ref "U5") (pin "6") (pinfunction "P2.0/C2D_6") (pintype "passive"))
    )
    (net (code "81") (name "/M4_CIN") (class "Default")
      (node (ref "R25") (pin "2") (pinfunction "2_2") (pintype "passive"))
      (node (ref "R48") (pin "1") (pinfunction "1_1") (pintype "passive"))
      (node (ref "R49") (pin "2") (pinfunction "2_2") (pintype "passive"))
      (node (ref "U5") (pin "1") (pinfunction "P0.1_1") (pintype "passive"))
    )
    (net (code "82") (name "/M4_HIN1") (class "Default")
      (node (ref "U5") (pin "14") (pinfunction "P1.0_14") (pintype "passive"))
      (node (ref "U9") (pin "22") (pinfunction "HIN1_22") (pintype "passive"))
    )
    (net (code "83") (name "/M4_HIN2") (class "Default")
      (node (ref "U5") (pin "13") (pinfunction "P1.1_13") (pintype "passive"))
      (node (ref "U9") (pin "23") (pinfunction "HIN2_23") (pintype "passive"))
    )
    (net (code "84") (name "/M4_HIN3") (class "Default")
      (node (ref "U5") (pin "11") (pinfunction "P1.2_11") (pintype "passive"))
      (node (ref "U9") (pin "24") (pinfunction "HIN3_24") (pintype "passive"))
    )
    (net (code "85") (name "/M4_HO1") (class "Default")
      (node (ref "R66") (pin "2") (pinfunction "2_2") (pintype "passive"))
      (node (ref "U9") (pin "19") (pinfunction "HO1_19") (pintype "passive"))
    )
    (net (code "86") (name "/M4_HO2") (class "Default")
      (node (ref "R55") (pin "2") (pinfunction "2_2") (pintype "passive"))
      (node (ref "U9") (pin "16") (pinfunction "HO2_16") (pintype "passive"))
    )
    (net (code "87") (name "/M4_HO3") (class "Default")
      (node (ref "R67") (pin "2") (pinfunction "2_2") (pintype "passive"))
      (node (ref "U9") (pin "13") (pinfunction "HO3_13") (pintype "passive"))
    )
    (net (code "88") (name "/M4_LIN1") (class "Default")
      (node (ref "U5") (pin "10") (pinfunction "P1.3_10") (pintype "passive"))
      (node (ref "U9") (pin "1") (pinfunction "LIN1_1") (pintype "passive"))
    )
    (net (code "89") (name "/M4_LIN2") (class "Default")
      (node (ref "U5") (pin "9") (pinfunction "P1.4_9") (pintype "passive"))
      (node (ref "U9") (pin "2") (pinfunction "LIN2_2") (pintype "passive"))
    )
    (net (code "90") (name "/M4_LIN3") (class "Default")
      (node (ref "U5") (pin "8") (pinfunction "P1.5_8") (pintype "passive"))
      (node (ref "U9") (pin "3") (pinfunction "LIN3_3") (pintype "passive"))
    )
    (net (code "91") (name "/M4_LO1") (class "Default")
      (node (ref "R72") (pin "2") (pinfunction "2_2") (pintype "passive"))
      (node (ref "U9") (pin "11") (pinfunction "LO1_11") (pintype "passive"))
    )
    (net (code "92") (name "/M4_LO2") (class "Default")
      (node (ref "R61") (pin "2") (pinfunction "2_2") (pintype "passive"))
      (node (ref "U9") (pin "10") (pinfunction "LO2_10") (pintype "passive"))
    )
    (net (code "93") (name "/M4_LO3") (class "Default")
      (node (ref "R73") (pin "2") (pinfunction "2_2") (pintype "passive"))
      (node (ref "U9") (pin "9") (pinfunction "LO3_9") (pintype "passive"))
    )
    (net (code "94") (name "/M4_PWM") (class "Default")
      (node (ref "P15") (pin "1") (pinfunction "1_1") (pintype "passive"))
      (node (ref "R13") (pin "2") (pinfunction "2_2") (pintype "passive"))
    )
    (net (code "95") (name "/M4_VB1") (class "Default")
      (node (ref "C26") (pin "2") (pinfunction "2_2") (pintype "passive"))
      (node (ref "D10") (pin "1") (pinfunction "K_1") (pintype "passive"))
      (node (ref "U9") (pin "20") (pinfunction "VB1_20") (pintype "passive"))
    )
    (net (code "96") (name "/M4_VB2") (class "Default")
      (node (ref "C27") (pin "2") (pinfunction "2_2") (pintype "passive"))
      (node (ref "D11") (pin "1") (pinfunction "K_1") (pintype "passive"))
      (node (ref "U9") (pin "17") (pinfunction "VB2_17") (pintype "passive"))
    )
    (net (code "97") (name "/M4_VB3") (class "Default")
      (node (ref "C28") (pin "2") (pinfunction "2_2") (pintype "passive"))
      (node (ref "D12") (pin "1") (pinfunction "K_1") (pintype "passive"))
      (node (ref "U9") (pin "14") (pinfunction "VB3_14") (pintype "passive"))
    )
    (net (code "98") (name "/M4_VS1") (class "Default")
      (node (ref "C26") (pin "1") (pinfunction "1_1") (pintype "passive"))
      (node (ref "P26") (pin "1") (pinfunction "1_1") (pintype "passive"))
      (node (ref "Q11") (pin "10") (pinfunction "S1/D2_10") (pintype "passive"))
      (node (ref "R32") (pin "2") (pinfunction "2_2") (pintype "passive"))
      (node (ref "U9") (pin "18") (pinfunction "VS1_18") (pintype "passive"))
    )
    (net (code "99") (name "/M4_VS2") (class "Default")
      (node (ref "C27") (pin "1") (pinfunction "1_1") (pintype "passive"))
      (node (ref "P21") (pin "1") (pinfunction "1_1") (pintype "passive"))
      (node (ref "Q6") (pin "10") (pinfunction "S1/D2_10") (pintype "passive"))
      (node (ref "R40") (pin "2") (pinfunction "2_2") (pintype "passive"))
      (node (ref "U9") (pin "15") (pinfunction "VS2_15") (pintype "passive"))
    )
    (net (code "100") (name "/M4_VS3") (class "Default")
      (node (ref "C28") (pin "1") (pinfunction "1_1") (pintype "passive"))
      (node (ref "P27") (pin "1") (pinfunction "1_1") (pintype "passive"))
      (node (ref "Q12") (pin "10") (pinfunction "S1/D2_10") (pintype "passive"))
      (node (ref "R48") (pin "2") (pinfunction "2_2") (pintype "passive"))
      (node (ref "U9") (pin "12") (pinfunction "VS3_12") (pintype "passive"))
    )
    (net (code "101") (name "9V") (class "Default")
      (node (ref "C13") (pin "2") (pinfunction "2_2") (pintype "passive"))
      (node (ref "C14") (pin "2") (pinfunction "2_2") (pintype "passive"))
      (node (ref "C15") (pin "2") (pinfunction "2_2") (pintype "passive"))
      (node (ref "C16") (pin "2") (pinfunction "2_2") (pintype "passive"))
      (node (ref "D1") (pin "2") (pinfunction "A_2") (pintype "passive"))
      (node (ref "D10") (pin "2") (pinfunction "A_2") (pintype "passive"))
      (node (ref "D11") (pin "2") (pinfunction "A_2") (pintype "passive"))
      (node (ref "D12") (pin "2") (pinfunction "A_2") (pintype "passive"))
      (node (ref "D2") (pin "2") (pinfunction "A_2") (pintype "passive"))
      (node (ref "D3") (pin "2") (pinfunction "A_2") (pintype "passive"))
      (node (ref "D4") (pin "2") (pinfunction "A_2") (pintype "passive"))
      (node (ref "D5") (pin "2") (pinfunction "A_2") (pintype "passive"))
      (node (ref "D6") (pin "2") (pinfunction "A_2") (pintype "passive"))
      (node (ref "D7") (pin "2") (pinfunction "A_2") (pintype "passive"))
      (node (ref "D8") (pin "2") (pinfunction "A_2") (pintype "passive"))
      (node (ref "D9") (pin "2") (pinfunction "A_2") (pintype "passive"))
      (node (ref "U6") (pin "4") (pinfunction "VCC_4") (pintype "passive"))
      (node (ref "U7") (pin "4") (pinfunction "VCC_4") (pintype "passive"))
      (node (ref "U8") (pin "4") (pinfunction "VCC_4") (pintype "passive"))
      (node (ref "U9") (pin "4") (pinfunction "VCC_4") (pintype "passive"))
    )
    (net (code "102") (name "GND") (class "Default")
      (node (ref "C10") (pin "2") (pinfunction "2_2") (pintype "passive"))
      (node (ref "C11") (pin "2") (pinfunction "2_2") (pintype "passive"))
      (node (ref "C12") (pin "2") (pinfunction "2_2") (pintype "passive"))
      (node (ref "C13") (pin "1") (pinfunction "1_1") (pintype "passive"))
      (node (ref "C14") (pin "1") (pinfunction "1_1") (pintype "passive"))
      (node (ref "C15") (pin "1") (pinfunction "1_1") (pintype "passive"))
      (node (ref "C16") (pin "1") (pinfunction "1_1") (pintype "passive"))
      (node (ref "C9") (pin "2") (pinfunction "2_2") (pintype "passive"))
      (node (ref "Q1") (pin "5") (pinfunction "S2_5") (pintype "passive"))
      (node (ref "Q1") (pin "6") (pinfunction "S2_6") (pintype "passive"))
      (node (ref "Q1") (pin "7") (pinfunction "S2_7") (pintype "passive"))
      (node (ref "Q10") (pin "5") (pinfunction "S2_5") (pintype "passive"))
      (node (ref "Q10") (pin "6") (pinfunction "S2_6") (pintype "passive"))
      (node (ref "Q10") (pin "7") (pinfunction "S2_7") (pintype "passive"))
      (node (ref "Q11") (pin "5") (pinfunction "S2_5") (pintype "passive"))
      (node (ref "Q11") (pin "6") (pinfunction "S2_6") (pintype "passive"))
      (node (ref "Q11") (pin "7") (pinfunction "S2_7") (pintype "passive"))
      (node (ref "Q12") (pin "5") (pinfunction "S2_5") (pintype "passive"))
      (node (ref "Q12") (pin "6") (pinfunction "S2_6") (pintype "passive"))
      (node (ref "Q12") (pin "7") (pinfunction "S2_7") (pintype "passive"))
      (node (ref "Q2") (pin "5") (pinfunction "S2_5") (pintype "passive"))
      (node (ref "Q2") (pin "6") (pinfunction "S2_6") (pintype "passive"))
      (node (ref "Q2") (pin "7") (pinfunction "S2_7") (pintype "passive"))
      (node (ref "Q3") (pin "5") (pinfunction "S2_5") (pintype "passive"))
      (node (ref "Q3") (pin "6") (pinfunction "S2_6") (pintype "passive"))
      (node (ref "Q3") (pin "7") (pinfunction "S2_7") (pintype "passive"))
      (node (ref "Q4") (pin "5") (pinfunction "S2_5") (pintype "passive"))
      (node (ref "Q4") (pin "6") (pinfunction "S2_6") (pintype "passive"))
      (node (ref "Q4") (pin "7") (pinfunction "S2_7") (pintype "passive"))
      (node (ref "Q5") (pin "5") (pinfunction "S2_5") (pintype "passive"))
      (node (ref "Q5") (pin "6") (pinfunction "S2_6") (pintype "passive"))
      (node (ref "Q5") (pin "7") (pinfunction "S2_7") (pintype "passive"))
      (node (ref "Q6") (pin "5") (pinfunction "S2_5") (pintype "passive"))
      (node (ref "Q6") (pin "6") (pinfunction "S2_6") (pintype "passive"))
      (node (ref "Q6") (pin "7") (pinfunction "S2_7") (pintype "passive"))
      (node (ref "Q7") (pin "5") (pinfunction "S2_5") (pintype "passive"))
      (node (ref "Q7") (pin "6") (pinfunction "S2_6") (pintype "passive"))
      (node (ref "Q7") (pin "7") (pinfunction "S2_7") (pintype "passive"))
      (node (ref "Q8") (pin "5") (pinfunction "S2_5") (pintype "passive"))
      (node (ref "Q8") (pin "6") (pinfunction "S2_6") (pintype "passive"))
      (node (ref "Q8") (pin "7") (pinfunction "S2_7") (pintype "passive"))
      (node (ref "Q9") (pin "5") (pinfunction "S2_5") (pintype "passive"))
      (node (ref "Q9") (pin "6") (pinfunction "S2_6") (pintype "passive"))
      (node (ref "Q9") (pin "7") (pinfunction "S2_7") (pintype "passive"))
      (node (ref "R27") (pin "1") (pinfunction "1_1") (pintype "passive"))
      (node (ref "R29") (pin "1") (pinfunction "1_1") (pintype "passive"))
      (node (ref "R31") (pin "1") (pinfunction "1_1") (pintype "passive"))
      (node (ref "R33") (pin "1") (pinfunction "1_1") (pintype "passive"))
      (node (ref "R35") (pin "1") (pinfunction "1_1") (pintype "passive"))
      (node (ref "R37") (pin "1") (pinfunction "1_1") (pintype "passive"))
      (node (ref "R39") (pin "1") (pinfunction "1_1") (pintype "passive"))
      (node (ref "R41") (pin "1") (pinfunction "1_1") (pintype "passive"))
      (node (ref "R43") (pin "1") (pinfunction "1_1") (pintype "passive"))
      (node (ref "R45") (pin "1") (pinfunction "1_1") (pintype "passive"))
      (node (ref "R47") (pin "1") (pinfunction "1_1") (pintype "passive"))
      (node (ref "R49") (pin "1") (pinfunction "1_1") (pintype "passive"))
      (node (ref "U2") (pin "12") (pinfunction "GND_12") (pintype "passive"))
      (node (ref "U2") (pin "21") (pinfunction "GND_21") (pintype "passive"))
      (node (ref "U2") (pin "3") (pinfunction "GND_3") (pintype "passive"))
      (node (ref "U3") (pin "12") (pinfunction "GND_12") (pintype "passive"))
      (node (ref "U3") (pin "21") (pinfunction "GND_21") (pintype "passive"))
      (node (ref "U3") (pin "3") (pinfunction "GND_3") (pintype "passive"))
      (node (ref "U4") (pin "12") (pinfunction "GND_12") (pintype "passive"))
      (node (ref "U4") (pin "21") (pinfunction "GND_21") (pintype "passive"))
      (node (ref "U4") (pin "3") (pinfunction "GND_3") (pintype "passive"))
      (node (ref "U5") (pin "12") (pinfunction "GND_12") (pintype "passive"))
      (node (ref "U5") (pin "21") (pinfunction "GND_21") (pintype "passive"))
      (node (ref "U5") (pin "3") (pinfunction "GND_3") (pintype "passive"))
      (node (ref "U6") (pin "25") (pinfunction "EP_25") (pintype "passive"))
      (node (ref "U6") (pin "6") (pinfunction "COM_6") (pintype "passive"))
      (node (ref "U7") (pin "25") (pinfunction "EP_25") (pintype "passive"))
      (node (ref "U7") (pin "6") (pinfunction "COM_6") (pintype "passive"))
      (node (ref "U8") (pin "25") (pinfunction "EP_25") (pintype "passive"))
      (node (ref "U8") (pin "6") (pinfunction "COM_6") (pintype "passive"))
      (node (ref "U9") (pin "25") (pinfunction "EP_25") (pintype "passive"))
      (node (ref "U9") (pin "6") (pinfunction "COM_6") (pintype "passive"))
    )
    (net (code "103") (name "Net-(Q1-G1)") (class "Default")
      (node (ref "Q1") (pin "1") (pinfunction "G1_1") (pintype "passive"))
      (node (ref "R50") (pin "1") (pinfunction "1_1") (pintype "passive"))
    )
    (net (code "104") (name "Net-(Q1-G2)") (class "Default")
      (node (ref "Q1") (pin "8") (pinfunction "G2_8") (pintype "passive"))
      (node (ref "R56") (pin "1") (pinfunction "1_1") (pintype "passive"))
    )
    (net (code "105") (name "Net-(Q2-G1)") (class "Default")
      (node (ref "Q2") (pin "1") (pinfunction "G1_1") (pintype "passive"))
      (node (ref "R51") (pin "1") (pinfunction "1_1") (pintype "passive"))
    )
    (net (code "106") (name "Net-(Q2-G2)") (class "Default")
      (node (ref "Q2") (pin "8") (pinfunction "G2_8") (pintype "passive"))
      (node (ref "R57") (pin "1") (pinfunction "1_1") (pintype "passive"))
    )
    (net (code "107") (name "Net-(Q3-G1)") (class "Default")
      (node (ref "Q3") (pin "1") (pinfunction "G1_1") (pintype "passive"))
      (node (ref "R52") (pin "1") (pinfunction "1_1") (pintype "passive"))
    )
    (net (code "108") (name "Net-(Q3-G2)") (class "Default")
      (node (ref "Q3") (pin "8") (pinfunction "G2_8") (pintype "passive"))
      (node (ref "R58") (pin "1") (pinfunction "1_1") (pintype "passive"))
    )
    (net (code "109") (name "Net-(Q4-G1)") (class "Default")
      (node (ref "Q4") (pin "1") (pinfunction "G1_1") (pintype "passive"))
      (node (ref "R53") (pin "1") (pinfunction "1_1") (pintype "passive"))
    )
    (net (code "110") (name "Net-(Q4-G2)") (class "Default")
      (node (ref "Q4") (pin "8") (pinfunction "G2_8") (pintype "passive"))
      (node (ref "R59") (pin "1") (pinfunction "1_1") (pintype "passive"))
    )
    (net (code "111") (name "Net-(Q5-G1)") (class "Default")
      (node (ref "Q5") (pin "1") (pinfunction "G1_1") (pintype "passive"))
      (node (ref "R54") (pin "1") (pinfunction "1_1") (pintype "passive"))
    )
    (net (code "112") (name "Net-(Q5-G2)") (class "Default")
      (node (ref "Q5") (pin "8") (pinfunction "G2_8") (pintype "passive"))
      (node (ref "R60") (pin "1") (pinfunction "1_1") (pintype "passive"))
    )
    (net (code "113") (name "Net-(Q6-G1)") (class "Default")
      (node (ref "Q6") (pin "1") (pinfunction "G1_1") (pintype "passive"))
      (node (ref "R55") (pin "1") (pinfunction "1_1") (pintype "passive"))
    )
    (net (code "114") (name "Net-(Q6-G2)") (class "Default")
      (node (ref "Q6") (pin "8") (pinfunction "G2_8") (pintype "passive"))
      (node (ref "R61") (pin "1") (pinfunction "1_1") (pintype "passive"))
    )
    (net (code "115") (name "Net-(Q7-G1)") (class "Default")
      (node (ref "Q7") (pin "1") (pinfunction "G1_1") (pintype "passive"))
      (node (ref "R62") (pin "1") (pinfunction "1_1") (pintype "passive"))
    )
    (net (code "116") (name "Net-(Q7-G2)") (class "Default")
      (node (ref "Q7") (pin "8") (pinfunction "G2_8") (pintype "passive"))
      (node (ref "R68") (pin "1") (pinfunction "1_1") (pintype "passive"))
    )
    (net (code "117") (name "Net-(Q8-G1)") (class "Default")
      (node (ref "Q8") (pin "1") (pinfunction "G1_1") (pintype "passive"))
      (node (ref "R63") (pin "1") (pinfunction "1_1") (pintype "passive"))
    )
    (net (code "118") (name "Net-(Q8-G2)") (class "Default")
      (node (ref "Q8") (pin "8") (pinfunction "G2_8") (pintype "passive"))
      (node (ref "R69") (pin "1") (pinfunction "1_1") (pintype "passive"))
    )
    (net (code "119") (name "Net-(Q9-G1)") (class "Default")
      (node (ref "Q9") (pin "1") (pinfunction "G1_1") (pintype "passive"))
      (node (ref "R64") (pin "1") (pinfunction "1_1") (pintype "passive"))
    )
    (net (code "120") (name "Net-(Q9-G2)") (class "Default")
      (node (ref "Q9") (pin "8") (pinfunction "G2_8") (pintype "passive"))
      (node (ref "R70") (pin "1") (pinfunction "1_1") (pintype "passive"))
    )
    (net (code "121") (name "Net-(Q10-G1)") (class "Default")
      (node (ref "Q10") (pin "1") (pinfunction "G1_1") (pintype "passive"))
      (node (ref "R65") (pin "1") (pinfunction "1_1") (pintype "passive"))
    )
    (net (code "122") (name "Net-(Q10-G2)") (class "Default")
      (node (ref "Q10") (pin "8") (pinfunction "G2_8") (pintype "passive"))
      (node (ref "R71") (pin "1") (pinfunction "1_1") (pintype "passive"))
    )
    (net (code "123") (name "Net-(Q11-G1)") (class "Default")
      (node (ref "Q11") (pin "1") (pinfunction "G1_1") (pintype "passive"))
      (node (ref "R66") (pin "1") (pinfunction "1_1") (pintype "passive"))
    )
    (net (code "124") (name "Net-(Q11-G2)") (class "Default")
      (node (ref "Q11") (pin "8") (pinfunction "G2_8") (pintype "passive"))
      (node (ref "R72") (pin "1") (pinfunction "1_1") (pintype "passive"))
    )
    (net (code "125") (name "Net-(Q12-G1)") (class "Default")
      (node (ref "Q12") (pin "1") (pinfunction "G1_1") (pintype "passive"))
      (node (ref "R67") (pin "1") (pinfunction "1_1") (pintype "passive"))
    )
    (net (code "126") (name "Net-(Q12-G2)") (class "Default")
      (node (ref "Q12") (pin "8") (pinfunction "G2_8") (pintype "passive"))
      (node (ref "R73") (pin "1") (pinfunction "1_1") (pintype "passive"))
    )
    (net (code "127") (name "Net-(U2-P0.4)") (class "Default")
      (node (ref "R10") (pin "1") (pinfunction "1_1") (pintype "passive"))
      (node (ref "U2") (pin "18") (pinfunction "P0.4_18") (pintype "passive"))
    )
    (net (code "128") (name "Net-(U3-P0.4)") (class "Default")
      (node (ref "R11") (pin "1") (pinfunction "1_1") (pintype "passive"))
      (node (ref "U3") (pin "18") (pinfunction "P0.4_18") (pintype "passive"))
    )
    (net (code "129") (name "Net-(U4-P0.4)") (class "Default")
      (node (ref "R12") (pin "1") (pinfunction "1_1") (pintype "passive"))
      (node (ref "U4") (pin "18") (pinfunction "P0.4_18") (pintype "passive"))
    )
    (net (code "130") (name "Net-(U5-P0.4)") (class "Default")
      (node (ref "R13") (pin "1") (pinfunction "1_1") (pintype "passive"))
      (node (ref "U5") (pin "18") (pinfunction "P0.4_18") (pintype "passive"))
    )
    (net (code "131") (name "Peripheral_3.3V") (class "Default")
      (node (ref "C10") (pin "1") (pinfunction "1_1") (pintype "passive"))
      (node (ref "C11") (pin "1") (pinfunction "1_1") (pintype "passive"))
      (node (ref "C12") (pin "1") (pinfunction "1_1") (pintype "passive"))
      (node (ref "C9") (pin "1") (pinfunction "1_1") (pintype "passive"))
      (node (ref "R6") (pin "1") (pinfunction "1_1") (pintype "passive"))
      (node (ref "R7") (pin "1") (pinfunction "1_1") (pintype "passive"))
      (node (ref "R8") (pin "1") (pinfunction "1_1") (pintype "passive"))
      (node (ref "R9") (pin "1") (pinfunction "1_1") (pintype "passive"))
      (node (ref "U2") (pin "4") (pinfunction "VDD_4") (pintype "passive"))
      (node (ref "U3") (pin "4") (pinfunction "VDD_4") (pintype "passive"))
      (node (ref "U4") (pin "4") (pinfunction "VDD_4") (pintype "passive"))
      (node (ref "U5") (pin "4") (pinfunction "VDD_4") (pintype "passive"))
    )
    (net (code "132") (name "VBAT") (class "Default")
      (node (ref "Q1") (pin "2") (pinfunction "D1_2") (pintype "passive"))
      (node (ref "Q1") (pin "3") (pinfunction "D1_3") (pintype "passive"))
      (node (ref "Q1") (pin "4") (pinfunction "D1_4") (pintype "passive"))
      (node (ref "Q1") (pin "9") (pinfunction "D1_9") (pintype "passive"))
      (node (ref "Q10") (pin "2") (pinfunction "D1_2") (pintype "passive"))
      (node (ref "Q10") (pin "3") (pinfunction "D1_3") (pintype "passive"))
      (node (ref "Q10") (pin "4") (pinfunction "D1_4") (pintype "passive"))
      (node (ref "Q10") (pin "9") (pinfunction "D1_9") (pintype "passive"))
      (node (ref "Q11") (pin "2") (pinfunction "D1_2") (pintype "passive"))
      (node (ref "Q11") (pin "3") (pinfunction "D1_3") (pintype "passive"))
      (node (ref "Q11") (pin "4") (pinfunction "D1_4") (pintype "passive"))
      (node (ref "Q11") (pin "9") (pinfunction "D1_9") (pintype "passive"))
      (node (ref "Q12") (pin "2") (pinfunction "D1_2") (pintype "passive"))
      (node (ref "Q12") (pin "3") (pinfunction "D1_3") (pintype "passive"))
      (node (ref "Q12") (pin "4") (pinfunction "D1_4") (pintype "passive"))
      (node (ref "Q12") (pin "9") (pinfunction "D1_9") (pintype "passive"))
      (node (ref "Q2") (pin "2") (pinfunction "D1_2") (pintype "passive"))
      (node (ref "Q2") (pin "3") (pinfunction "D1_3") (pintype "passive"))
      (node (ref "Q2") (pin "4") (pinfunction "D1_4") (pintype "passive"))
      (node (ref "Q2") (pin "9") (pinfunction "D1_9") (pintype "passive"))
      (node (ref "Q3") (pin "2") (pinfunction "D1_2") (pintype "passive"))
      (node (ref "Q3") (pin "3") (pinfunction "D1_3") (pintype "passive"))
      (node (ref "Q3") (pin "4") (pinfunction "D1_4") (pintype "passive"))
      (node (ref "Q3") (pin "9") (pinfunction "D1_9") (pintype "passive"))
      (node (ref "Q4") (pin "2") (pinfunction "D1_2") (pintype "passive"))
      (node (ref "Q4") (pin "3") (pinfunction "D1_3") (pintype "passive"))
      (node (ref "Q4") (pin "4") (pinfunction "D1_4") (pintype "passive"))
      (node (ref "Q4") (pin "9") (pinfunction "D1_9") (pintype "passive"))
      (node (ref "Q5") (pin "2") (pinfunction "D1_2") (pintype "passive"))
      (node (ref "Q5") (pin "3") (pinfunction "D1_3") (pintype "passive"))
      (node (ref "Q5") (pin "4") (pinfunction "D1_4") (pintype "passive"))
      (node (ref "Q5") (pin "9") (pinfunction "D1_9") (pintype "passive"))
      (node (ref "Q6") (pin "2") (pinfunction "D1_2") (pintype "passive"))
      (node (ref "Q6") (pin "3") (pinfunction "D1_3") (pintype "passive"))
      (node (ref "Q6") (pin "4") (pinfunction "D1_4") (pintype "passive"))
      (node (ref "Q6") (pin "9") (pinfunction "D1_9") (pintype "passive"))
      (node (ref "Q7") (pin "2") (pinfunction "D1_2") (pintype "passive"))
      (node (ref "Q7") (pin "3") (pinfunction "D1_3") (pintype "passive"))
      (node (ref "Q7") (pin "4") (pinfunction "D1_4") (pintype "passive"))
      (node (ref "Q7") (pin "9") (pinfunction "D1_9") (pintype "passive"))
      (node (ref "Q8") (pin "2") (pinfunction "D1_2") (pintype "passive"))
      (node (ref "Q8") (pin "3") (pinfunction "D1_3") (pintype "passive"))
      (node (ref "Q8") (pin "4") (pinfunction "D1_4") (pintype "passive"))
      (node (ref "Q8") (pin "9") (pinfunction "D1_9") (pintype "passive"))
      (node (ref "Q9") (pin "2") (pinfunction "D1_2") (pintype "passive"))
      (node (ref "Q9") (pin "3") (pinfunction "D1_3") (pintype "passive"))
      (node (ref "Q9") (pin "4") (pinfunction "D1_4") (pintype "passive"))
      (node (ref "Q9") (pin "9") (pinfunction "D1_9") (pintype "passive"))
    )
    (net (code "133") (name "unconnected-(U2-P0.5-Pad17)") (class "Default")
      (node (ref "U2") (pin "17") (pinfunction "P0.5_17") (pintype "passive+no_connect"))
    )
    (net (code "134") (name "unconnected-(U2-P0.6-Pad16)") (class "Default")
      (node (ref "U2") (pin "16") (pinfunction "P0.6_16") (pintype "passive+no_connect"))
    )
    (net (code "135") (name "unconnected-(U2-P0.7-Pad15)") (class "Default")
      (node (ref "U2") (pin "15") (pinfunction "P0.7_15") (pintype "passive+no_connect"))
    )
    (net (code "136") (name "unconnected-(U2-P1.6-Pad7)") (class "Default")
      (node (ref "U2") (pin "7") (pinfunction "P1.6_7") (pintype "passive+no_connect"))
    )
    (net (code "137") (name "unconnected-(U3-P0.5-Pad17)") (class "Default")
      (node (ref "U3") (pin "17") (pinfunction "P0.5_17") (pintype "passive+no_connect"))
    )
    (net (code "138") (name "unconnected-(U3-P0.6-Pad16)") (class "Default")
      (node (ref "U3") (pin "16") (pinfunction "P0.6_16") (pintype "passive+no_connect"))
    )
    (net (code "139") (name "unconnected-(U3-P0.7-Pad15)") (class "Default")
      (node (ref "U3") (pin "15") (pinfunction "P0.7_15") (pintype "passive+no_connect"))
    )
    (net (code "140") (name "unconnected-(U3-P1.6-Pad7)") (class "Default")
      (node (ref "U3") (pin "7") (pinfunction "P1.6_7") (pintype "passive+no_connect"))
    )
    (net (code "141") (name "unconnected-(U4-P0.5-Pad17)") (class "Default")
      (node (ref "U4") (pin "17") (pinfunction "P0.5_17") (pintype "passive+no_connect"))
    )
    (net (code "142") (name "unconnected-(U4-P0.6-Pad16)") (class "Default")
      (node (ref "U4") (pin "16") (pinfunction "P0.6_16") (pintype "passive+no_connect"))
    )
    (net (code "143") (name "unconnected-(U4-P0.7-Pad15)") (class "Default")
      (node (ref "U4") (pin "15") (pinfunction "P0.7_15") (pintype "passive+no_connect"))
    )
    (net (code "144") (name "unconnected-(U4-P1.6-Pad7)") (class "Default")
      (node (ref "U4") (pin "7") (pinfunction "P1.6_7") (pintype "passive+no_connect"))
    )
    (net (code "145") (name "unconnected-(U5-P0.5-Pad17)") (class "Default")
      (node (ref "U5") (pin "17") (pinfunction "P0.5_17") (pintype "passive+no_connect"))
    )
    (net (code "146") (name "unconnected-(U5-P0.6-Pad16)") (class "Default")
      (node (ref "U5") (pin "16") (pinfunction "P0.6_16") (pintype "passive+no_connect"))
    )
    (net (code "147") (name "unconnected-(U5-P0.7-Pad15)") (class "Default")
      (node (ref "U5") (pin "15") (pinfunction "P0.7_15") (pintype "passive+no_connect"))
    )
    (net (code "148") (name "unconnected-(U5-P1.6-Pad7)") (class "Default")
      (node (ref "U5") (pin "7") (pinfunction "P1.6_7") (pintype "passive+no_connect"))
    )
    (net (code "149") (name "unconnected-(U6-NC-Pad5)") (class "Default")
      (node (ref "U6") (pin "5") (pinfunction "NC_5") (pintype "passive+no_connect"))
    )
    (net (code "150") (name "unconnected-(U6-NC-Pad7)") (class "Default")
      (node (ref "U6") (pin "7") (pinfunction "NC_7") (pintype "passive+no_connect"))
    )
    (net (code "151") (name "unconnected-(U6-NC-Pad8)") (class "Default")
      (node (ref "U6") (pin "8") (pinfunction "NC_8") (pintype "passive+no_connect"))
    )
    (net (code "152") (name "unconnected-(U6-NC-Pad21)") (class "Default")
      (node (ref "U6") (pin "21") (pinfunction "NC_21") (pintype "passive+no_connect"))
    )
    (net (code "153") (name "unconnected-(U7-NC-Pad5)") (class "Default")
      (node (ref "U7") (pin "5") (pinfunction "NC_5") (pintype "passive+no_connect"))
    )
    (net (code "154") (name "unconnected-(U7-NC-Pad7)") (class "Default")
      (node (ref "U7") (pin "7") (pinfunction "NC_7") (pintype "passive+no_connect"))
    )
    (net (code "155") (name "unconnected-(U7-NC-Pad8)") (class "Default")
      (node (ref "U7") (pin "8") (pinfunction "NC_8") (pintype "passive+no_connect"))
    )
    (net (code "156") (name "unconnected-(U7-NC-Pad21)") (class "Default")
      (node (ref "U7") (pin "21") (pinfunction "NC_21") (pintype "passive+no_connect"))
    )
    (net (code "157") (name "unconnected-(U8-NC-Pad5)") (class "Default")
      (node (ref "U8") (pin "5") (pinfunction "NC_5") (pintype "passive+no_connect"))
    )
    (net (code "158") (name "unconnected-(U8-NC-Pad7)") (class "Default")
      (node (ref "U8") (pin "7") (pinfunction "NC_7") (pintype "passive+no_connect"))
    )
    (net (code "159") (name "unconnected-(U8-NC-Pad8)") (class "Default")
      (node (ref "U8") (pin "8") (pinfunction "NC_8") (pintype "passive+no_connect"))
    )
    (net (code "160") (name "unconnected-(U8-NC-Pad21)") (class "Default")
      (node (ref "U8") (pin "21") (pinfunction "NC_21") (pintype "passive+no_connect"))
    )
    (net (code "161") (name "unconnected-(U9-NC-Pad5)") (class "Default")
      (node (ref "U9") (pin "5") (pinfunction "NC_5") (pintype "passive+no_connect"))
    )
    (net (code "162") (name "unconnected-(U9-NC-Pad7)") (class "Default")
      (node (ref "U9") (pin "7") (pinfunction "NC_7") (pintype "passive+no_connect"))
    )
    (net (code "163") (name "unconnected-(U9-NC-Pad8)") (class "Default")
      (node (ref "U9") (pin "8") (pinfunction "NC_8") (pintype "passive+no_connect"))
    )
    (net (code "164") (name "unconnected-(U9-NC-Pad21)") (class "Default")
      (node (ref "U9") (pin "21") (pinfunction "NC_21") (pintype "passive+no_connect"))
    )
  )
)
